# USB_To_Uart_3V3.net
KiCad netlist of a schematic drawn in EAGLE
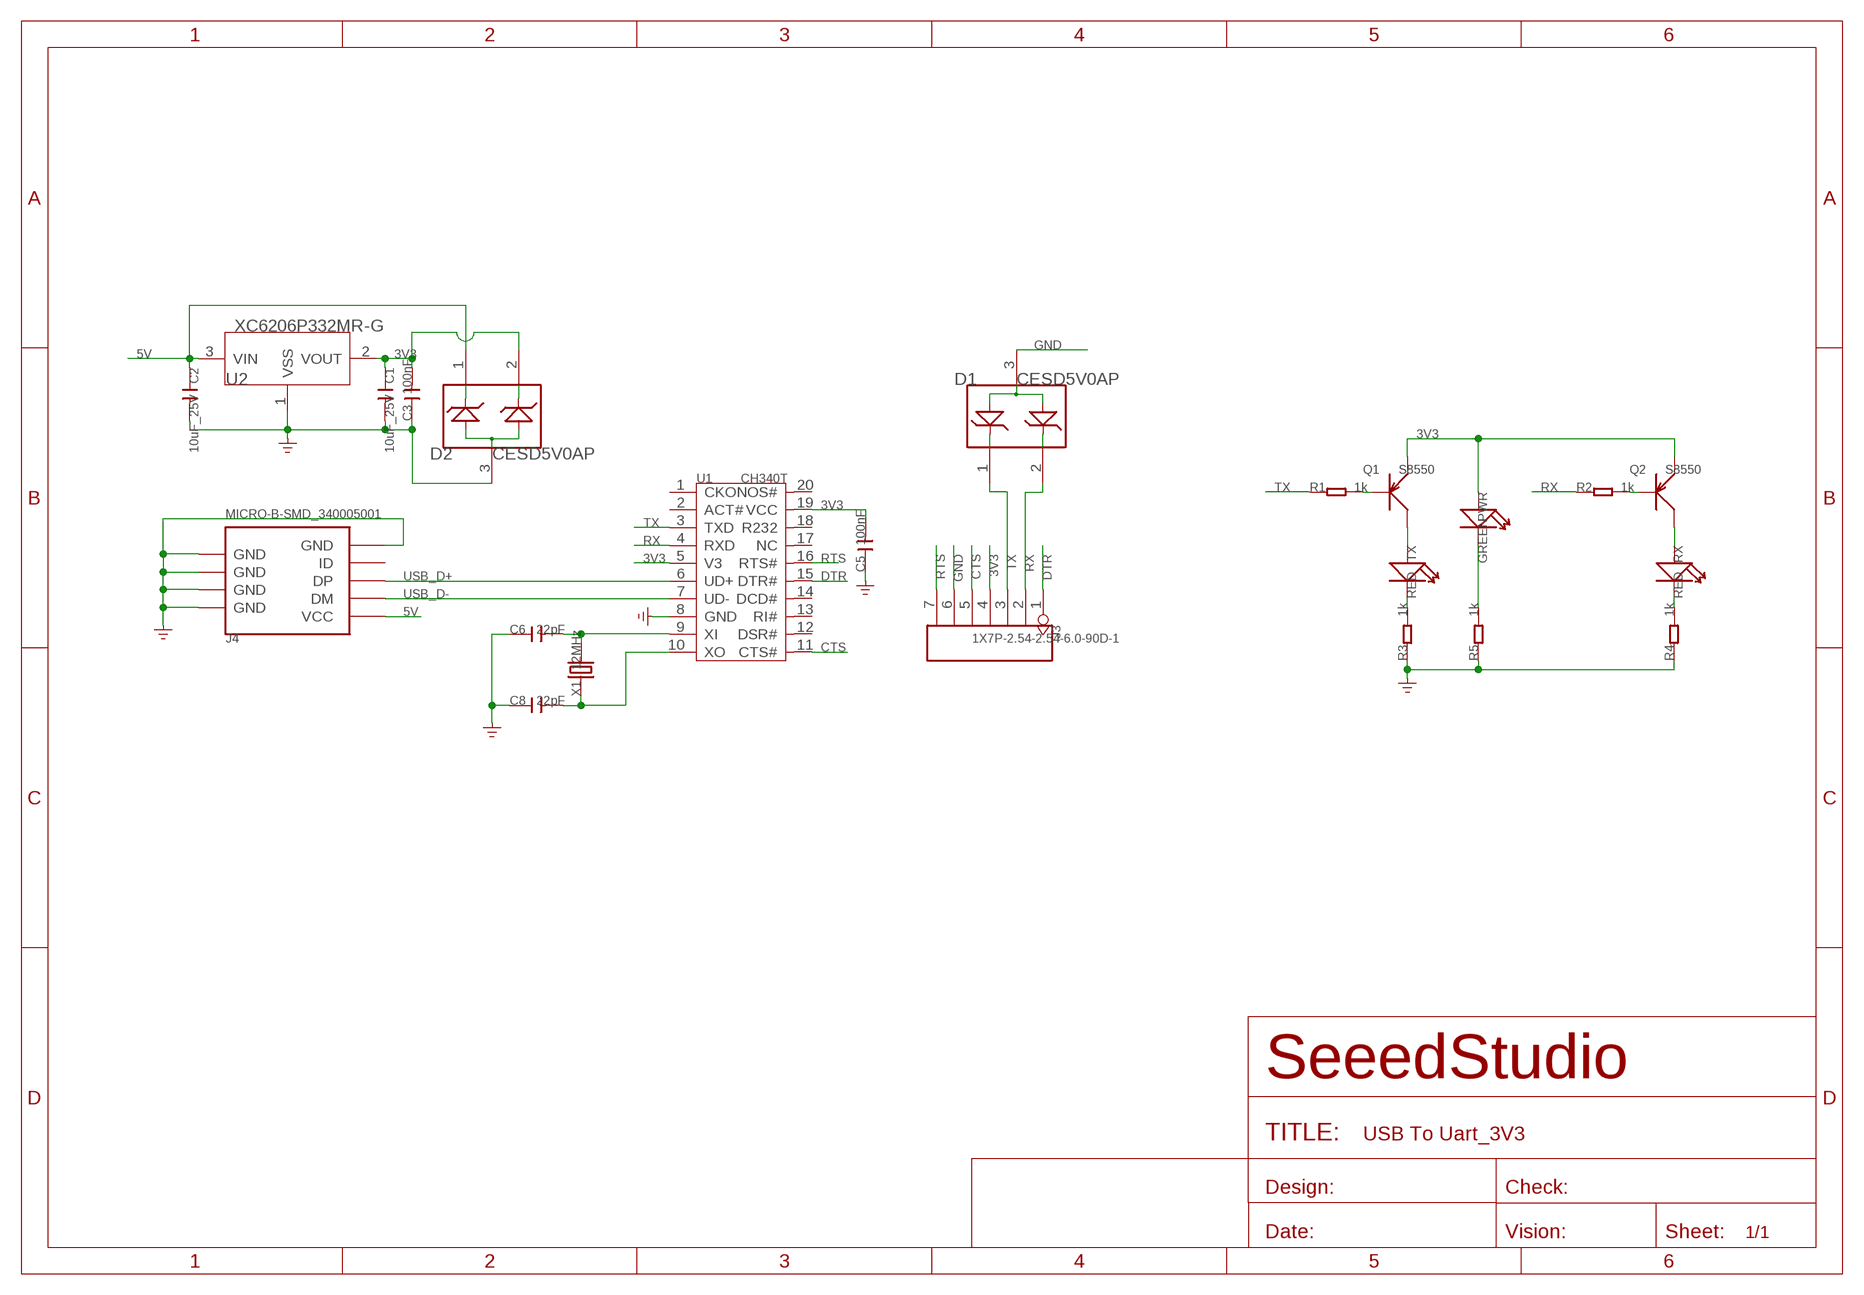
[diagram p0: schematic, sheet 1]

(export (version "E")
  (design (tool "Eeschema 10.0.6"))
  (components
    (comp (ref "C1")
      (value "10uF_25V")
      (footprint "eagle-import:C0805")
      (libsource (lib "eagle-import") (part "C-0805"))
    )
    (comp (ref "C2")
      (value "10uF_25V")
      (footprint "eagle-import:C0805")
      (libsource (lib "eagle-import") (part "C-0805"))
    )
    (comp (ref "C3")
      (value "100nF")
      (footprint "eagle-import:C0402")
      (libsource (lib "eagle-import") (part "C-0402"))
    )
    (comp (ref "C5")
      (value "100nF")
      (footprint "eagle-import:C0402")
      (libsource (lib "eagle-import") (part "C-0402"))
    )
    (comp (ref "C6")
      (value "22pF")
      (footprint "eagle-import:C0402")
      (libsource (lib "eagle-import") (part "C-0402"))
    )
    (comp (ref "C8")
      (value "22pF")
      (footprint "eagle-import:C0402")
      (libsource (lib "eagle-import") (part "C-0402"))
    )
    (comp (ref "D1")
      (value "CESD5V0AP")
      (footprint "eagle-import:SOT23")
      (libsource (lib "eagle-import") (part "D-ESD-3P"))
    )
    (comp (ref "D2")
      (value "CESD5V0AP")
      (footprint "eagle-import:SOT23")
      (libsource (lib "eagle-import") (part "D-ESD-3P"))
    )
    (comp (ref "J3")
      (value "1X7P-2.54-2.54-6.0-90D-1")
      (footprint "eagle-import:7P-2.54-65_35MIL")
      (libsource (lib "eagle-import") (part "HEADER-7P"))
    )
    (comp (ref "J4")
      (value "MICRO-B-SMD_340005001")
      (footprint "eagle-import:MICRO-USB")
      (libsource (lib "eagle-import") (part "USB-MINIUSB-5P-MICRO"))
    )
    (comp (ref "PWR")
      (value "GREEN")
      (footprint "eagle-import:LED-0603")
      (libsource (lib "eagle-import") (part "LED'0603'"))
    )
    (comp (ref "Q1")
      (value "S8550")
      (footprint "eagle-import:SOT23")
      (libsource (lib "eagle-import") (part "TRANSISTOR-PNP-SOT23"))
    )
    (comp (ref "Q2")
      (value "S8550")
      (footprint "eagle-import:SOT23")
      (libsource (lib "eagle-import") (part "TRANSISTOR-PNP-SOT23"))
    )
    (comp (ref "R1")
      (value "1k")
      (footprint "eagle-import:R0402")
      (libsource (lib "eagle-import") (part "R-0402"))
    )
    (comp (ref "R2")
      (value "1k")
      (footprint "eagle-import:R0402")
      (libsource (lib "eagle-import") (part "R-0402"))
    )
    (comp (ref "R3")
      (value "1k")
      (footprint "eagle-import:R0402")
      (libsource (lib "eagle-import") (part "R-0402"))
    )
    (comp (ref "R4")
      (value "1k")
      (footprint "eagle-import:R0402")
      (libsource (lib "eagle-import") (part "R-0402"))
    )
    (comp (ref "R5")
      (value "1k")
      (footprint "eagle-import:R0402")
      (libsource (lib "eagle-import") (part "R-0402"))
    )
    (comp (ref "RX")
      (value "RED")
      (footprint "eagle-import:LED-0603")
      (libsource (lib "eagle-import") (part "LED'0603'"))
    )
    (comp (ref "TX")
      (value "RED")
      (footprint "eagle-import:LED-0603")
      (libsource (lib "eagle-import") (part "LED'0603'"))
    )
    (comp (ref "U1")
      (value "CH340T")
      (footprint "eagle-import:SSOP20")
      (libsource (lib "eagle-import") (part "CH340T"))
    )
    (comp (ref "U2")
      (value "XC6206P332MR-G")
      (footprint "eagle-import:SOT23")
      (libsource (lib "eagle-import") (part "XC6206MR"))
    )
    (comp (ref "X1")
      (value "12MHz")
      (footprint "eagle-import:HC49UP")
      (libsource (lib "eagle-import") (part "CRYSTAL'HC49UP'"))
    )
  )
  (nets
    (net (code "1") (name "/3V3") (class "Default")
      (node (ref "C1") (pin "1") (pinfunction "1_1") (pintype "passive"))
      (node (ref "C3") (pin "2") (pinfunction "2_2") (pintype "passive"))
      (node (ref "C5") (pin "2") (pinfunction "2_2") (pintype "passive"))
      (node (ref "D2") (pin "2") (pinfunction "2_2") (pintype "bidirectional"))
      (node (ref "J3") (pin "4") (pinfunction "4_4") (pintype "bidirectional"))
      (node (ref "PWR") (pin "+") (pinfunction "+_+") (pintype "passive"))
      (node (ref "Q1") (pin "2") (pinfunction "E_2") (pintype "passive"))
      (node (ref "Q2") (pin "2") (pinfunction "E_2") (pintype "passive"))
      (node (ref "U1") (pin "19") (pinfunction "VCC_19") (pintype "power_in"))
      (node (ref "U1") (pin "5") (pinfunction "V3_5") (pintype "power_in"))
      (node (ref "U2") (pin "2") (pinfunction "VOUT_2") (pintype "output"))
    )
    (net (code "2") (name "/5V") (class "Default")
      (node (ref "C2") (pin "1") (pinfunction "1_1") (pintype "passive"))
      (node (ref "D2") (pin "1") (pinfunction "1_1") (pintype "bidirectional"))
      (node (ref "J4") (pin "1") (pinfunction "VCC_1") (pintype "bidirectional"))
      (node (ref "U2") (pin "3") (pinfunction "VIN_3") (pintype "input"))
    )
    (net (code "3") (name "/CTS") (class "Default")
      (node (ref "J3") (pin "5") (pinfunction "5_5") (pintype "bidirectional"))
      (node (ref "U1") (pin "11") (pinfunction "CTS#_11") (pintype "input"))
    )
    (net (code "4") (name "/DTR") (class "Default")
      (node (ref "J3") (pin "1") (pinfunction "1_1") (pintype "bidirectional"))
      (node (ref "U1") (pin "15") (pinfunction "DTR#_15") (pintype "output"))
    )
    (net (code "5") (name "/NOS#") (class "Default")
      (node (ref "U1") (pin "20") (pinfunction "NOS#_20") (pintype "power_in"))
    )
    (net (code "6") (name "/RTS") (class "Default")
      (node (ref "J3") (pin "7") (pinfunction "7_7") (pintype "bidirectional"))
      (node (ref "U1") (pin "16") (pinfunction "RTS#_16") (pintype "output"))
    )
    (net (code "7") (name "/RX") (class "Default")
      (node (ref "D1") (pin "2") (pinfunction "2_2") (pintype "bidirectional"))
      (node (ref "J3") (pin "2") (pinfunction "2_2") (pintype "bidirectional"))
      (node (ref "R2") (pin "1") (pinfunction "1_1") (pintype "passive"))
      (node (ref "U1") (pin "4") (pinfunction "RXD_4") (pintype "input"))
    )
    (net (code "8") (name "/TX") (class "Default")
      (node (ref "D1") (pin "1") (pinfunction "1_1") (pintype "bidirectional"))
      (node (ref "J3") (pin "3") (pinfunction "3_3") (pintype "bidirectional"))
      (node (ref "R1") (pin "1") (pinfunction "1_1") (pintype "passive"))
      (node (ref "U1") (pin "3") (pinfunction "TXD_3") (pintype "output"))
    )
    (net (code "9") (name "/USB_D+") (class "Default")
      (node (ref "J4") (pin "3") (pinfunction "DP_3") (pintype "bidirectional"))
      (node (ref "U1") (pin "6") (pinfunction "UD+_6") (pintype "bidirectional"))
    )
    (net (code "10") (name "/USB_D-") (class "Default")
      (node (ref "J4") (pin "2") (pinfunction "DM_2") (pintype "bidirectional"))
      (node (ref "U1") (pin "7") (pinfunction "UD-_7") (pintype "bidirectional"))
    )
    (net (code "11") (name "GND_POWER") (class "Default")
      (node (ref "C1") (pin "2") (pinfunction "2_2") (pintype "passive"))
      (node (ref "C2") (pin "2") (pinfunction "2_2") (pintype "passive"))
      (node (ref "C3") (pin "1") (pinfunction "1_1") (pintype "passive"))
      (node (ref "C5") (pin "1") (pinfunction "1_1") (pintype "passive"))
      (node (ref "C6") (pin "1") (pinfunction "1_1") (pintype "passive"))
      (node (ref "C8") (pin "1") (pinfunction "1_1") (pintype "passive"))
      (node (ref "D1") (pin "3") (pinfunction "3_3") (pintype "bidirectional"))
      (node (ref "D2") (pin "3") (pinfunction "3_3") (pintype "bidirectional"))
      (node (ref "J3") (pin "6") (pinfunction "6_6") (pintype "bidirectional"))
      (node (ref "J4") (pin "5") (pinfunction "GND_5") (pintype "bidirectional"))
      (node (ref "J4") (pin "S1") (pinfunction "GND_S1") (pintype "bidirectional"))
      (node (ref "J4") (pin "S2") (pinfunction "GND_S2") (pintype "bidirectional"))
      (node (ref "J4") (pin "S3") (pinfunction "GND_S3") (pintype "bidirectional"))
      (node (ref "J4") (pin "S4") (pinfunction "GND_S4") (pintype "bidirectional"))
      (node (ref "J4") (pin "S5") (pinfunction "GND_S5") (pintype "bidirectional"))
      (node (ref "J4") (pin "S6") (pinfunction "GND_S6") (pintype "bidirectional"))
      (node (ref "R3") (pin "1") (pinfunction "1_1") (pintype "passive"))
      (node (ref "R4") (pin "1") (pinfunction "1_1") (pintype "passive"))
      (node (ref "R5") (pin "1") (pinfunction "1_1") (pintype "passive"))
      (node (ref "U1") (pin "8") (pinfunction "GND_8") (pintype "power_in"))
      (node (ref "U2") (pin "1") (pinfunction "VSS_1") (pintype "power_in"))
    )
    (net (code "12") (name "Net-(PWR-Pad-)") (class "Default")
      (node (ref "PWR") (pin "-") (pinfunction "-_-") (pintype "passive"))
      (node (ref "R5") (pin "2") (pinfunction "2_2") (pintype "passive"))
    )
    (net (code "13") (name "Net-(Q1-B)") (class "Default")
      (node (ref "Q1") (pin "1") (pinfunction "B_1") (pintype "passive"))
      (node (ref "R1") (pin "2") (pinfunction "2_2") (pintype "passive"))
    )
    (net (code "14") (name "Net-(Q1-C)") (class "Default")
      (node (ref "Q1") (pin "3") (pinfunction "C_3") (pintype "passive"))
      (node (ref "TX") (pin "+") (pinfunction "+_+") (pintype "passive"))
    )
    (net (code "15") (name "Net-(Q2-B)") (class "Default")
      (node (ref "Q2") (pin "1") (pinfunction "B_1") (pintype "passive"))
      (node (ref "R2") (pin "2") (pinfunction "2_2") (pintype "passive"))
    )
    (net (code "16") (name "Net-(Q2-C)") (class "Default")
      (node (ref "Q2") (pin "3") (pinfunction "C_3") (pintype "passive"))
      (node (ref "RX") (pin "+") (pinfunction "+_+") (pintype "passive"))
    )
    (net (code "17") (name "Net-(R3-Pad2)") (class "Default")
      (node (ref "R3") (pin "2") (pinfunction "2_2") (pintype "passive"))
      (node (ref "TX") (pin "-") (pinfunction "-_-") (pintype "passive"))
    )
    (net (code "18") (name "Net-(R4-Pad2)") (class "Default")
      (node (ref "R4") (pin "2") (pinfunction "2_2") (pintype "passive"))
      (node (ref "RX") (pin "-") (pinfunction "-_-") (pintype "passive"))
    )
    (net (code "19") (name "Net-(U1-XI)") (class "Default")
      (node (ref "C6") (pin "2") (pinfunction "2_2") (pintype "passive"))
      (node (ref "U1") (pin "9") (pinfunction "XI_9") (pintype "input"))
      (node (ref "X1") (pin "2") (pinfunction "2_2") (pintype "passive"))
    )
    (net (code "20") (name "Net-(U1-XO)") (class "Default")
      (node (ref "C8") (pin "2") (pinfunction "2_2") (pintype "passive"))
      (node (ref "U1") (pin "10") (pinfunction "XO_10") (pintype "output"))
      (node (ref "X1") (pin "1") (pinfunction "1_1") (pintype "passive"))
    )
    (net (code "21") (name "unconnected-(J4-ID-Pad4)") (class "Default")
      (node (ref "J4") (pin "4") (pinfunction "ID_4") (pintype "bidirectional"))
    )
    (net (code "22") (name "unconnected-(U1-ACT#-Pad2)") (class "Default")
      (node (ref "U1") (pin "2") (pinfunction "ACT#_2") (pintype "output"))
    )
    (net (code "23") (name "unconnected-(U1-CKO-Pad1)") (class "Default")
      (node (ref "U1") (pin "1") (pinfunction "CKO_1") (pintype "output"))
    )
    (net (code "24") (name "unconnected-(U1-DCD#-Pad14)") (class "Default")
      (node (ref "U1") (pin "14") (pinfunction "DCD#_14") (pintype "input"))
    )
    (net (code "25") (name "unconnected-(U1-DSR#-Pad12)") (class "Default")
      (node (ref "U1") (pin "12") (pinfunction "DSR#_12") (pintype "input"))
    )
    (net (code "26") (name "unconnected-(U1-NC-Pad17)") (class "Default")
      (node (ref "U1") (pin "17") (pinfunction "NC_17") (pintype "no_connect"))
    )
    (net (code "27") (name "unconnected-(U1-R232-Pad18)") (class "Default")
      (node (ref "U1") (pin "18") (pinfunction "R232_18") (pintype "input"))
    )
    (net (code "28") (name "unconnected-(U1-RI#-Pad13)") (class "Default")
      (node (ref "U1") (pin "13") (pinfunction "RI#_13") (pintype "input"))
    )
  )
)
